# gfci-tester.net
KiCad netlist of a schematic drawn in EAGLE
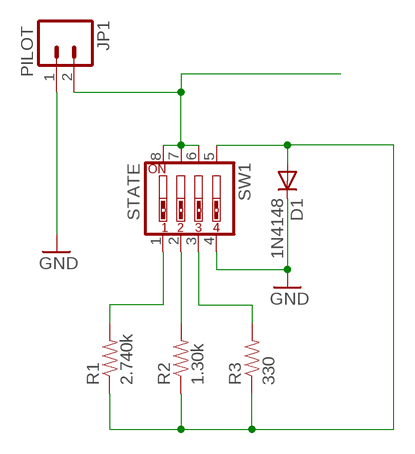
[diagram p0: schematic, sheet 1]

(export (version "E")
  (design (tool "Eeschema 10.0.6"))
  (components
    (comp (ref "D1")
      (value "1N4148")
      (footprint "eagle-import:DIODE-1N4148")
      (libsource (lib "eagle-import") (part "DIODE1N4148"))
    )
    (comp (ref "JP1")
      (value "PILOT")
      (footprint "eagle-import:SCREWTERMINAL-3.5MM-2_LOCK")
      (libsource (lib "eagle-import") (part "M023.5MM_LOCK"))
    )
    (comp (ref "R1")
      (value "2.740k")
      (footprint "eagle-import:AXIAL-0.4")
      (libsource (lib "eagle-import") (part "RESISTORPTH-1/4W"))
    )
    (comp (ref "R2")
      (value "1.30k")
      (footprint "eagle-import:AXIAL-0.4")
      (libsource (lib "eagle-import") (part "RESISTORPTH-1/4W"))
    )
    (comp (ref "R3")
      (value "330")
      (footprint "eagle-import:AXIAL-0.4")
      (libsource (lib "eagle-import") (part "RESISTORPTH-1/4W"))
    )
    (comp (ref "SW1")
      (value "STATE")
      (footprint "eagle-import:EDG-04")
      (libsource (lib "eagle-import") (part "SW_DIP-4"))
    )
  )
  (nets
    (net (code "1") (name "GND") (class "Default")
      (node (ref "D1") (pin "C") (pinfunction "C_C") (pintype "passive"))
      (node (ref "JP1") (pin "1") (pinfunction "1_1") (pintype "passive"))
      (node (ref "SW1") (pin "4") (pinfunction "4_4") (pintype "passive"))
    )
    (net (code "2") (name "Net-(JP1-Pad2)") (class "Default")
      (node (ref "JP1") (pin "2") (pinfunction "2_2") (pintype "passive"))
      (node (ref "SW1") (pin "6") (pinfunction "6_6") (pintype "passive"))
      (node (ref "SW1") (pin "7") (pinfunction "7_7") (pintype "passive"))
      (node (ref "SW1") (pin "8") (pinfunction "8_8") (pintype "passive"))
    )
    (net (code "3") (name "Net-(R1-1)") (class "Default")
      (node (ref "D1") (pin "A") (pinfunction "A_A") (pintype "passive"))
      (node (ref "R1") (pin "P$1") (pinfunction "1_P$1") (pintype "passive"))
      (node (ref "R2") (pin "P$1") (pinfunction "1_P$1") (pintype "passive"))
      (node (ref "R3") (pin "P$1") (pinfunction "1_P$1") (pintype "passive"))
      (node (ref "SW1") (pin "5") (pinfunction "5_5") (pintype "passive"))
    )
    (net (code "4") (name "Net-(R1-2)") (class "Default")
      (node (ref "R1") (pin "P$2") (pinfunction "2_P$2") (pintype "passive"))
      (node (ref "SW1") (pin "1") (pinfunction "1_1") (pintype "passive"))
    )
    (net (code "5") (name "Net-(R2-2)") (class "Default")
      (node (ref "R2") (pin "P$2") (pinfunction "2_P$2") (pintype "passive"))
      (node (ref "SW1") (pin "2") (pinfunction "2_2") (pintype "passive"))
    )
    (net (code "6") (name "Net-(R3-2)") (class "Default")
      (node (ref "R3") (pin "P$2") (pinfunction "2_P$2") (pintype "passive"))
      (node (ref "SW1") (pin "3") (pinfunction "3_3") (pintype "passive"))
    )
  )
)
